# FPGA_PD.net
KiCad netlist of a schematic drawn in Altium Designer
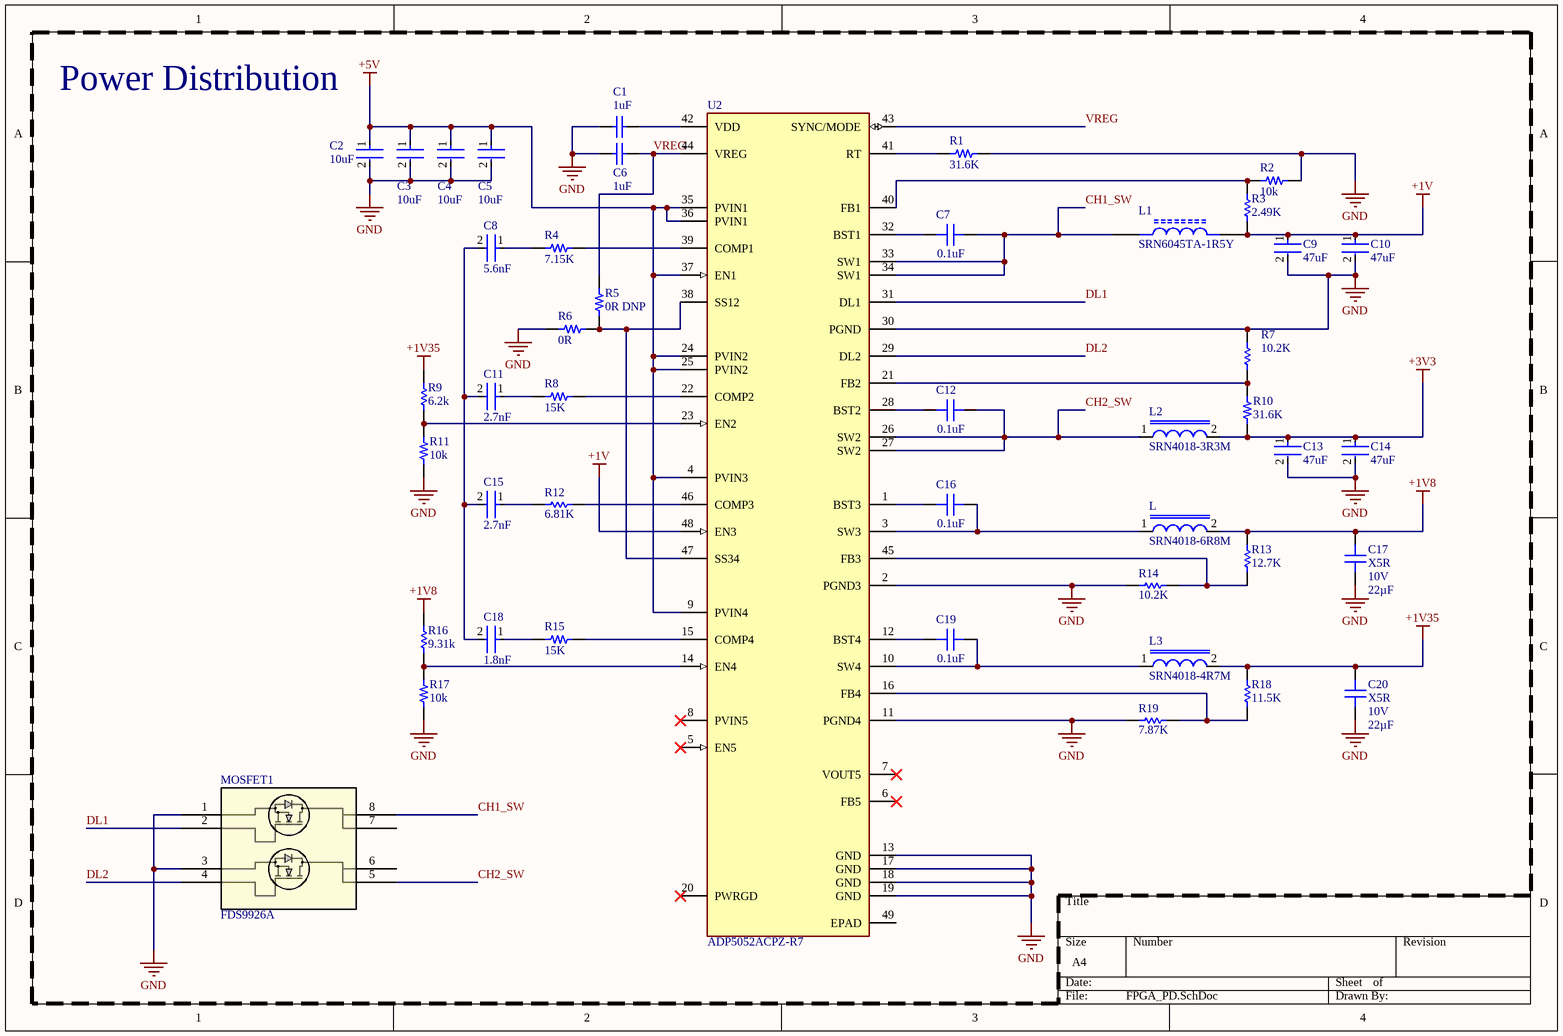
[diagram p0: FPGA_PD.SchDoc]

(export (version "E")
  (design (tool "Eeschema 10.0.6"))
  (components
    (comp (ref "C1")
      (value "1uF")
      (footprint "CAPC1005X55X25LL05T10")
      (fields (field (name "MANUFACTURER") "Murata") (field (name "PART NUMBER") "GRM155R71C104KA88J"))
      (libsource (lib "BIG_FPGA") (part "CMP-2008-03928-1"))
    )
    (comp (ref "C2")
      (value "10uF")
      (footprint "FP-GRM155-0_2-IPC_A")
      (description "Chip Multilayer Ceramic Capacitors for General Purpose, 0402, 10uF, X5R, 15%, 20%, 10V")
      (libsource (lib "BIG_FPGA") (part "CMP-06035-026070-1"))
    )
    (comp (ref "C3")
      (value "10uF")
      (footprint "FP-GRM155-0_2-IPC_A")
      (description "Chip Multilayer Ceramic Capacitors for General Purpose, 0402, 10uF, X5R, 15%, 20%, 10V")
      (libsource (lib "BIG_FPGA") (part "CMP-06035-026070-1"))
    )
    (comp (ref "C4")
      (value "10uF")
      (footprint "FP-GRM155-0_2-IPC_A")
      (description "Chip Multilayer Ceramic Capacitors for General Purpose, 0402, 10uF, X5R, 15%, 20%, 10V")
      (libsource (lib "BIG_FPGA") (part "CMP-06035-026070-1"))
    )
    (comp (ref "C5")
      (value "10uF")
      (footprint "FP-GRM155-0_2-IPC_A")
      (description "Chip Multilayer Ceramic Capacitors for General Purpose, 0402, 10uF, X5R, 15%, 20%, 10V")
      (libsource (lib "BIG_FPGA") (part "CMP-06035-026070-1"))
    )
    (comp (ref "C6")
      (value "1uF")
      (footprint "CAPC1005X55X25LL05T10")
      (fields (field (name "MANUFACTURER") "Murata") (field (name "PART NUMBER") "GRM155R71C104KA88J"))
      (libsource (lib "BIG_FPGA") (part "CMP-2008-03928-1"))
    )
    (comp (ref "C7")
      (value "CAP CER 0.1UF 100V 10% X7R 0603")
      (footprint "CAP 0603_1608")
      (fields (field (name "CAPACITANCE") "0.1uF") (field (name "TOLERANCE") "10%"))
      (libsource (lib "Midnight Sun") (part "Capacitor"))
    )
    (comp (ref "C8")
      (value "5.6nF")
      (footprint "FP-GRM188-0_1-e0_2_0_5-IPC_A")
      (description "Chip Multilayer Ceramic Capacitors for General Purpose, 0603, 5600pF, C0G, 30ppm/°C, 5%, 50V")
      (fields (field (name "TOLERANCE") "5%"))
      (libsource (lib "Altium Content Vault") (part "11868f565c42a9108669ba33697ecf6"))
    )
    (comp (ref "C9")
      (value "47uF")
      (footprint "FP-GRM21B-0_2-MFG")
      (description "CAP CER 47UF 6.3V X5R 0805")
      (fields (field (name "TOLERANCE") "20%") (field (name "VOLTAGE") "6.3V"))
      (libsource (lib "Altium Content Vault") (part "02cd4be3c70576c341d710602a673aa"))
    )
    (comp (ref "C10")
      (value "47uF")
      (footprint "FP-GRM21B-0_2-MFG")
      (description "CAP CER 47UF 6.3V X5R 0805")
      (fields (field (name "TOLERANCE") "20%") (field (name "VOLTAGE") "6.3V"))
      (libsource (lib "Altium Content Vault") (part "02cd4be3c70576c341d710602a673aa"))
    )
    (comp (ref "C11")
      (value "2.7nF")
      (footprint "FP-GRM188-0_1-e0_2_0_5-MFG")
      (description "Chip Multilayer Ceramic Capacitors for General Purpose, 0603, 2700pF, C0G, 30ppm/°C, 5%, 50V")
      (fields (field (name "VOLTAGE") "50V") (field (name "TOLERANCE") "5%"))
      (libsource (lib "Altium Content Vault") (part "11868f565c42a9108669ba33697ecf6"))
    )
    (comp (ref "C12")
      (value "CAP CER 0.1UF 100V 10% X7R 0603")
      (footprint "CAP 0603_1608")
      (fields (field (name "CAPACITANCE") "0.1uF") (field (name "TOLERANCE") "10%"))
      (libsource (lib "Midnight Sun") (part "Capacitor"))
    )
    (comp (ref "C13")
      (value "47uF")
      (footprint "FP-GRM21B-0_2-MFG")
      (description "CAP CER 47UF 6.3V X5R 0805")
      (fields (field (name "TOLERANCE") "20%") (field (name "VOLTAGE") "6.3V"))
      (libsource (lib "Altium Content Vault") (part "02cd4be3c70576c341d710602a673aa"))
    )
    (comp (ref "C14")
      (value "47uF")
      (footprint "FP-GRM21B-0_2-MFG")
      (description "CAP CER 47UF 6.3V X5R 0805")
      (fields (field (name "TOLERANCE") "20%") (field (name "VOLTAGE") "6.3V"))
      (libsource (lib "Altium Content Vault") (part "02cd4be3c70576c341d710602a673aa"))
    )
    (comp (ref "C15")
      (value "2.7nF")
      (footprint "FP-GRM188-0_1-e0_2_0_5-MFG")
      (description "Chip Multilayer Ceramic Capacitors for General Purpose, 0603, 2700pF, C0G, 30ppm/°C, 5%, 50V")
      (fields (field (name "VOLTAGE") "50V") (field (name "TOLERANCE") "5%"))
      (libsource (lib "Altium Content Vault") (part "11868f565c42a9108669ba33697ecf6"))
    )
    (comp (ref "C16")
      (value "CAP CER 0.1UF 100V 10% X7R 0603")
      (footprint "CAP 0603_1608")
      (fields (field (name "CAPACITANCE") "0.1uF") (field (name "TOLERANCE") "10%"))
      (libsource (lib "Midnight Sun") (part "Capacitor"))
    )
    (comp (ref "C17")
      (value "CAP CER 22UF 10V 20% X5R 0603")
      (footprint "CAP 0603_1608")
      (fields
        (field (name "DIELECTRIC CODE") "X5R")
        (field (name "VOLTAGE RATING") "10V")
        (field (name "CAPACITANCE") "22µF")
        (field (name "TOLERANCE") "20%")
      )
      (libsource (lib "Midnight Sun") (part "Capacitor"))
    )
    (comp (ref "C18")
      (value "1.8nF")
      (footprint "FP-GRM188-0_1-e0_2_0_5-IPC_B")
      (description "Chip Multilayer Ceramic Capacitors for General Purpose, 0603, 1800pF, C0G, 30ppm/°C, 5%, 50V")
      (fields (field (name "VOLTAGE") "50V") (field (name "TOLERANCE") "5%"))
      (libsource (lib "Altium Content Vault") (part "11868f565c42a9108669ba33697ecf6"))
    )
    (comp (ref "C19")
      (value "CAP CER 0.1UF 100V 10% X7R 0603")
      (footprint "CAP 0603_1608")
      (fields (field (name "CAPACITANCE") "0.1uF") (field (name "TOLERANCE") "10%"))
      (libsource (lib "Midnight Sun") (part "Capacitor"))
    )
    (comp (ref "C20")
      (value "CAP CER 22UF 10V 20% X5R 0603")
      (footprint "CAP 0603_1608")
      (fields
        (field (name "DIELECTRIC CODE") "X5R")
        (field (name "VOLTAGE RATING") "10V")
        (field (name "CAPACITANCE") "22µF")
        (field (name "TOLERANCE") "20%")
      )
      (libsource (lib "Midnight Sun") (part "Capacitor"))
    )
    (comp (ref "L")
      (value "SRN4018-6R8M")
      (footprint "INDP4040X180N - duplicate")
      (description "6.8ÂµH Semi-Shielded Wirewound Inductor 1.5A 118mOhm Max Nonstandard")
      (fields (field (name "MF") "Bourns"))
      (libsource (lib "BIG_FPGA") (part "SRN4018-6R8M"))
    )
    (comp (ref "L1")
      (value "SRN6045TA-1R5Y")
      (footprint "IND_SRN6045TA-1R5Y")
      (libsource (lib "BIG_FPGA") (part "SRN6045TA-1R5Y"))
    )
    (comp (ref "L2")
      (value "SRN4018-3R3M")
      (footprint "INDP4040X180N - duplicate")
      (description "3.3ÂµH Semi-Shielded Wirewound Inductor 2.2A 66mOhm Max Nonstandard")
      (fields (field (name "MF") "Bourns"))
      (libsource (lib "BIG_FPGA") (part "SRN4018-3R3M"))
    )
    (comp (ref "L3")
      (value "SRN4018-4R7M")
      (footprint "FP-SRN4018-MFG")
      (description "FIXED IND 4.7UH 1.9A 84 MOHM SMD")
      (fields
        (field (name "OCTOPART") "https://octopart.com/srn4018-4r7m-bourns-25452396")
        (field (name "TOLERANCE") "20%")
      )
      (libsource (lib "BIG_FPGA") (part "CMP-07248-000014-1"))
    )
    (comp (ref "MOSFET1")
      (value "FDS9926A")
      (footprint "SOIC8_751EB_ONS-M")
      (description "No Description Available")
      (libsource (lib "BIG_FPGA") (part "FDS9926A"))
    )
    (comp (ref "R1")
      (value "31.6K")
      (footprint "RES 0603_1608")
      (libsource (lib "Midnight Sun") (part "Resistor"))
    )
    (comp (ref "R2")
      (value "10k")
      (footprint "RES 0603_1608")
      (description "10 ±1% 0.1W, 1/10W Chip Resistor 0603 (1608 Metric) Automotive AEC-Q200 Thick Film")
      (libsource (lib "Midnight Sun") (part "Resistor"))
    )
    (comp (ref "R3")
      (value "2.49K")
      (footprint "RESC1608X55X30ML20T20")
      (fields (field (name "PART NUMBER") "ERA3AEB2491V") (field (name "MANUFACTURER") "Panasonic"))
      (libsource (lib "Altium Content Vault") (part "RES"))
    )
    (comp (ref "R4")
      (value "7.15K")
      (footprint "FP-AC0603-IPC_A")
      (description "RES 7.15KΩ 1.00% 0.1W 0603")
      (fields (field (name "TOLERANCE") "1%"))
      (libsource (lib "BIG_FPGA") (part "CMP-03412-024834-2"))
    )
    (comp (ref "R5")
      (value "0R DNP")
      (footprint "RES 0603_1608")
      (description "Fixed Resistor, Metal Glaze/thick Film, 0.1W, 0ohm, Surface Mount, 0603")
      (libsource (lib "Midnight Sun") (part "Resistor"))
    )
    (comp (ref "R6")
      (value "0R")
      (footprint "RES 0603_1608")
      (description "Fixed Resistor, Metal Glaze/thick Film, 0.1W, 0ohm, Surface Mount, 0603")
      (libsource (lib "Midnight Sun") (part "Resistor"))
    )
    (comp (ref "R7")
      (value "10.2K")
      (footprint "RESC1608X55X25LL10T15")
      (description "Chip Resistor, 10.2 KOhm, +/- 1%, 0.1 W, -55 to 155 degC, 0603 (1608 Metric), RoHS, Tape and Reel")
      (fields (field (name "TOLERANCE") "1%") (field (name "MANUFACTURER") "Yageo"))
      (libsource (lib "Altium Content Vault") (part "RES-2"))
    )
    (comp (ref "R8")
      (value "15K")
      (footprint "RES 0603_1608")
      (description "15 kOhms ±1% 0.1W, 1/10W Chip Resistor 0603 (1608 Metric) Moisture Resistant Thick Film")
      (libsource (lib "Midnight Sun") (part "Resistor"))
    )
    (comp (ref "R9")
      (value "6.2k")
      (footprint "RESC1608X55X25ML10T15")
      (fields (field (name "PART NUMBER") "RC0603JR-076K2L") (field (name "MANUFACTURER") "Yageo"))
      (libsource (lib "Altium Content Vault") (part "RES"))
    )
    (comp (ref "R10")
      (value "31.6K")
      (footprint "RES 0603_1608")
      (libsource (lib "Midnight Sun") (part "Resistor"))
    )
    (comp (ref "R11")
      (value "10k")
      (footprint "RES 0603_1608")
      (description "10 ±1% 0.1W, 1/10W Chip Resistor 0603 (1608 Metric) Automotive AEC-Q200 Thick Film")
      (libsource (lib "Midnight Sun") (part "Resistor"))
    )
    (comp (ref "R12")
      (value "6.81K")
      (footprint "RESC1608X55X25ML10T15")
      (fields (field (name "PART NUMBER") "RC0603FR-076K81L") (field (name "MANUFACTURER") "Yageo"))
      (libsource (lib "Altium Content Vault") (part "RES"))
    )
    (comp (ref "R13")
      (value "12.7K")
      (footprint "RESC1608X55X30LL15T15")
      (fields (field (name "MANUFACTURER") "Panasonic") (field (name "PART NUMBER") "ERJ-3EKF1272V"))
      (libsource (lib "Altium Content Vault") (part "RES"))
    )
    (comp (ref "R14")
      (value "10.2K")
      (footprint "RESC1608X55X25LL10T15")
      (description "Chip Resistor, 10.2 KOhm, +/- 1%, 0.1 W, -55 to 155 degC, 0603 (1608 Metric), RoHS, Tape and Reel")
      (fields (field (name "TOLERANCE") "1%") (field (name "MANUFACTURER") "Yageo"))
      (libsource (lib "Altium Content Vault") (part "RES-2"))
    )
    (comp (ref "R15")
      (value "15K")
      (footprint "RES 0603_1608")
      (description "15 kOhms ±1% 0.1W, 1/10W Chip Resistor 0603 (1608 Metric) Moisture Resistant Thick Film")
      (libsource (lib "Midnight Sun") (part "Resistor"))
    )
    (comp (ref "R16")
      (value "9.31k")
      (footprint "RESC1608X55X25LL10T15")
      (fields (field (name "PART NUMBER") "RC0603FR-079K31L") (field (name "MANUFACTURER") "Yageo"))
      (libsource (lib "Altium Content Vault") (part "RES"))
    )
    (comp (ref "R17")
      (value "10k")
      (footprint "RES 0603_1608")
      (description "10 ±1% 0.1W, 1/10W Chip Resistor 0603 (1608 Metric) Automotive AEC-Q200 Thick Film")
      (libsource (lib "Midnight Sun") (part "Resistor"))
    )
    (comp (ref "R18")
      (value "11.5K")
      (footprint "RESC1608X55X25LL10T15")
      (fields (field (name "MANUFACTURER") "Yageo") (field (name "PART NUMBER") "RC0603FR-0711K5L"))
      (libsource (lib "Altium Content Vault") (part "RES"))
    )
    (comp (ref "R19")
      (value "7.87K")
      (footprint "RESC1608X55X25NL10T15")
      (fields (field (name "PART NUMBER") "RC0603FR-07787KL") (field (name "MANUFACTURER") "Yageo"))
      (libsource (lib "Altium Content Vault") (part "RES"))
    )
    (comp (ref "U2")
      (value "ADP5052ACPZ-R7")
      (footprint "FP-CP-48-13-IPC_A")
      (libsource (lib "Altium Content Vault") (part "c99ea894cd2d839e347de8f837bd5fd"))
    )
  )
  (nets
    (net (code "1") (name "+1V") (class "Default")
      (node (ref "C10") (pin "1") (pinfunction "1_1") (pintype "passive"))
      (node (ref "C9") (pin "1") (pinfunction "1_1") (pintype "passive"))
      (node (ref "L1") (pin "2") (pinfunction "2_2") (pintype "passive"))
      (node (ref "R3") (pin "1") (pinfunction "1_1") (pintype "passive"))
      (node (ref "U2") (pin "48") (pinfunction "EN3_48") (pintype "input"))
    )
    (net (code "2") (name "+1V8") (class "Default")
      (node (ref "C17") (pin "1") (pinfunction "1_1") (pintype "passive"))
      (node (ref "L") (pin "2") (pinfunction "2_2") (pintype "passive"))
      (node (ref "R13") (pin "2") (pinfunction "2_2") (pintype "passive"))
      (node (ref "R16") (pin "1") (pinfunction "1_1") (pintype "passive"))
    )
    (net (code "3") (name "+1V35") (class "Default")
      (node (ref "C20") (pin "1") (pinfunction "1_1") (pintype "passive"))
      (node (ref "L3") (pin "2") (pinfunction "2_2") (pintype "passive"))
      (node (ref "R18") (pin "1") (pinfunction "1_1") (pintype "passive"))
      (node (ref "R9") (pin "1") (pinfunction "1_1") (pintype "passive"))
    )
    (net (code "4") (name "+3V3") (class "Default")
      (node (ref "C13") (pin "1") (pinfunction "1_1") (pintype "passive"))
      (node (ref "C14") (pin "1") (pinfunction "1_1") (pintype "passive"))
      (node (ref "L2") (pin "2") (pinfunction "2_2") (pintype "passive"))
      (node (ref "R10") (pin "2") (pinfunction "2_2") (pintype "passive"))
    )
    (net (code "5") (name "+5V") (class "Default")
      (node (ref "C2") (pin "1") (pinfunction "1_1") (pintype "passive"))
      (node (ref "C3") (pin "1") (pinfunction "1_1") (pintype "passive"))
      (node (ref "C4") (pin "1") (pinfunction "1_1") (pintype "passive"))
      (node (ref "C5") (pin "1") (pinfunction "1_1") (pintype "passive"))
      (node (ref "U2") (pin "24") (pinfunction "PVIN2_24") (pintype "power_in"))
      (node (ref "U2") (pin "25") (pinfunction "PVIN2_25") (pintype "power_in"))
      (node (ref "U2") (pin "35") (pinfunction "PVIN1_35") (pintype "power_in"))
      (node (ref "U2") (pin "36") (pinfunction "PVIN1_36") (pintype "power_in"))
      (node (ref "U2") (pin "37") (pinfunction "EN1_37") (pintype "input"))
      (node (ref "U2") (pin "4") (pinfunction "PVIN3_4") (pintype "power_in"))
      (node (ref "U2") (pin "9") (pinfunction "PVIN4_9") (pintype "power_in"))
    )
    (net (code "6") (name "/CH1_SW") (class "Default")
      (node (ref "C7") (pin "1") (pinfunction "1_1") (pintype "passive"))
      (node (ref "L1") (pin "1") (pinfunction "1_1") (pintype "passive"))
      (node (ref "MOSFET1") (pin "8") (pinfunction "8_8") (pintype "passive"))
      (node (ref "U2") (pin "33") (pinfunction "SW1_33") (pintype "power_in"))
      (node (ref "U2") (pin "34") (pinfunction "SW1_34") (pintype "power_in"))
    )
    (net (code "7") (name "/CH2_SW") (class "Default")
      (node (ref "C12") (pin "1") (pinfunction "1_1") (pintype "passive"))
      (node (ref "L2") (pin "1") (pinfunction "1_1") (pintype "passive"))
      (node (ref "MOSFET1") (pin "5") (pinfunction "5_5") (pintype "passive"))
      (node (ref "U2") (pin "26") (pinfunction "SW2_26") (pintype "power_in"))
      (node (ref "U2") (pin "27") (pinfunction "SW2_27") (pintype "power_in"))
    )
    (net (code "8") (name "/DL1") (class "Default")
      (node (ref "MOSFET1") (pin "2") (pinfunction "2_2") (pintype "passive"))
      (node (ref "U2") (pin "31") (pinfunction "DL1_31") (pintype "passive"))
    )
    (net (code "9") (name "/DL2") (class "Default")
      (node (ref "MOSFET1") (pin "4") (pinfunction "4_4") (pintype "passive"))
      (node (ref "U2") (pin "29") (pinfunction "DL2_29") (pintype "passive"))
    )
    (net (code "10") (name "/VREG") (class "Default")
      (node (ref "C6") (pin "2") (pinfunction "2_2") (pintype "passive"))
      (node (ref "R5") (pin "2") (pinfunction "2_2") (pintype "passive"))
      (node (ref "U2") (pin "43") (pinfunction "SYNC/MODE_43") (pintype "bidirectional"))
      (node (ref "U2") (pin "44") (pinfunction "VREG_44") (pintype "power_in"))
    )
    (net (code "11") (name "GND") (class "Default")
      (node (ref "C1") (pin "1") (pinfunction "1_1") (pintype "passive"))
      (node (ref "C10") (pin "2") (pinfunction "2_2") (pintype "passive"))
      (node (ref "C13") (pin "2") (pinfunction "2_2") (pintype "passive"))
      (node (ref "C14") (pin "2") (pinfunction "2_2") (pintype "passive"))
      (node (ref "C17") (pin "2") (pinfunction "2_2") (pintype "passive"))
      (node (ref "C2") (pin "2") (pinfunction "2_2") (pintype "passive"))
      (node (ref "C20") (pin "2") (pinfunction "2_2") (pintype "passive"))
      (node (ref "C3") (pin "2") (pinfunction "2_2") (pintype "passive"))
      (node (ref "C4") (pin "2") (pinfunction "2_2") (pintype "passive"))
      (node (ref "C5") (pin "2") (pinfunction "2_2") (pintype "passive"))
      (node (ref "C6") (pin "1") (pinfunction "1_1") (pintype "passive"))
      (node (ref "C9") (pin "2") (pinfunction "2_2") (pintype "passive"))
      (node (ref "MOSFET1") (pin "1") (pinfunction "1_1") (pintype "passive"))
      (node (ref "MOSFET1") (pin "3") (pinfunction "3_3") (pintype "passive"))
      (node (ref "R1") (pin "2") (pinfunction "2_2") (pintype "passive"))
      (node (ref "R11") (pin "2") (pinfunction "2_2") (pintype "passive"))
      (node (ref "R14") (pin "2") (pinfunction "2_2") (pintype "passive"))
      (node (ref "R17") (pin "2") (pinfunction "2_2") (pintype "passive"))
      (node (ref "R19") (pin "1") (pinfunction "1_1") (pintype "passive"))
      (node (ref "R2") (pin "1") (pinfunction "1_1") (pintype "passive"))
      (node (ref "R6") (pin "1") (pinfunction "1_1") (pintype "passive"))
      (node (ref "R7") (pin "1") (pinfunction "1_1") (pintype "passive"))
      (node (ref "U2") (pin "11") (pinfunction "PGND4_11") (pintype "power_in"))
      (node (ref "U2") (pin "13") (pinfunction "GND_13") (pintype "power_in"))
      (node (ref "U2") (pin "17") (pinfunction "GND_17") (pintype "power_in"))
      (node (ref "U2") (pin "18") (pinfunction "GND_18") (pintype "power_in"))
      (node (ref "U2") (pin "19") (pinfunction "GND_19") (pintype "power_in"))
      (node (ref "U2") (pin "2") (pinfunction "PGND3_2") (pintype "power_in"))
      (node (ref "U2") (pin "30") (pinfunction "PGND_30") (pintype "power_in"))
    )
    (net (code "12") (name "Net-(C8-Pad1)") (class "Default")
      (node (ref "C8") (pin "1") (pinfunction "1_1") (pintype "passive"))
      (node (ref "R4") (pin "1") (pinfunction "1_1") (pintype "passive"))
    )
    (net (code "13") (name "Net-(C11-Pad1)") (class "Default")
      (node (ref "C11") (pin "1") (pinfunction "1_1") (pintype "passive"))
      (node (ref "R8") (pin "1") (pinfunction "1_1") (pintype "passive"))
    )
    (net (code "14") (name "Net-(C11-Pad2)") (class "Default")
      (node (ref "C11") (pin "2") (pinfunction "2_2") (pintype "passive"))
      (node (ref "C15") (pin "2") (pinfunction "2_2") (pintype "passive"))
      (node (ref "C18") (pin "2") (pinfunction "2_2") (pintype "passive"))
      (node (ref "C8") (pin "2") (pinfunction "2_2") (pintype "passive"))
    )
    (net (code "15") (name "Net-(C15-Pad1)") (class "Default")
      (node (ref "C15") (pin "1") (pinfunction "1_1") (pintype "passive"))
      (node (ref "R12") (pin "1") (pinfunction "1_1") (pintype "passive"))
    )
    (net (code "16") (name "Net-(C18-Pad1)") (class "Default")
      (node (ref "C18") (pin "1") (pinfunction "1_1") (pintype "passive"))
      (node (ref "R15") (pin "1") (pinfunction "1_1") (pintype "passive"))
    )
    (net (code "17") (name "Net-(U2-BST1)") (class "Default")
      (node (ref "C7") (pin "2") (pinfunction "2_2") (pintype "passive"))
      (node (ref "U2") (pin "32") (pinfunction "BST1_32") (pintype "power_in"))
    )
    (net (code "18") (name "Net-(U2-BST2)") (class "Default")
      (node (ref "C12") (pin "2") (pinfunction "2_2") (pintype "passive"))
      (node (ref "U2") (pin "28") (pinfunction "BST2_28") (pintype "power_in"))
    )
    (net (code "19") (name "Net-(U2-BST3)") (class "Default")
      (node (ref "C16") (pin "2") (pinfunction "2_2") (pintype "passive"))
      (node (ref "U2") (pin "1") (pinfunction "BST3_1") (pintype "power_in"))
    )
    (net (code "20") (name "Net-(U2-BST4)") (class "Default")
      (node (ref "C19") (pin "2") (pinfunction "2_2") (pintype "passive"))
      (node (ref "U2") (pin "12") (pinfunction "BST4_12") (pintype "power_in"))
    )
    (net (code "21") (name "Net-(U2-COMP1)") (class "Default")
      (node (ref "R4") (pin "2") (pinfunction "2_2") (pintype "passive"))
      (node (ref "U2") (pin "39") (pinfunction "COMP1_39") (pintype "passive"))
    )
    (net (code "22") (name "Net-(U2-COMP2)") (class "Default")
      (node (ref "R8") (pin "2") (pinfunction "2_2") (pintype "passive"))
      (node (ref "U2") (pin "22") (pinfunction "COMP2_22") (pintype "passive"))
    )
    (net (code "23") (name "Net-(U2-COMP3)") (class "Default")
      (node (ref "R12") (pin "2") (pinfunction "2_2") (pintype "passive"))
      (node (ref "U2") (pin "46") (pinfunction "COMP3_46") (pintype "passive"))
    )
    (net (code "24") (name "Net-(U2-COMP4)") (class "Default")
      (node (ref "R15") (pin "2") (pinfunction "2_2") (pintype "passive"))
      (node (ref "U2") (pin "15") (pinfunction "COMP4_15") (pintype "passive"))
    )
    (net (code "25") (name "Net-(U2-EN2)") (class "Default")
      (node (ref "R11") (pin "1") (pinfunction "1_1") (pintype "passive"))
      (node (ref "R9") (pin "2") (pinfunction "2_2") (pintype "passive"))
      (node (ref "U2") (pin "23") (pinfunction "EN2_23") (pintype "input"))
    )
    (net (code "26") (name "Net-(U2-EN4)") (class "Default")
      (node (ref "R16") (pin "2") (pinfunction "2_2") (pintype "passive"))
      (node (ref "R17") (pin "1") (pinfunction "1_1") (pintype "passive"))
      (node (ref "U2") (pin "14") (pinfunction "EN4_14") (pintype "input"))
    )
    (net (code "27") (name "Net-(U2-FB1)") (class "Default")
      (node (ref "R2") (pin "2") (pinfunction "2_2") (pintype "passive"))
      (node (ref "R3") (pin "2") (pinfunction "2_2") (pintype "passive"))
      (node (ref "U2") (pin "40") (pinfunction "FB1_40") (pintype "passive"))
    )
    (net (code "28") (name "Net-(U2-FB2)") (class "Default")
      (node (ref "R10") (pin "1") (pinfunction "1_1") (pintype "passive"))
      (node (ref "R7") (pin "2") (pinfunction "2_2") (pintype "passive"))
      (node (ref "U2") (pin "21") (pinfunction "FB2_21") (pintype "passive"))
    )
    (net (code "29") (name "Net-(U2-FB3)") (class "Default")
      (node (ref "R13") (pin "1") (pinfunction "1_1") (pintype "passive"))
      (node (ref "R14") (pin "1") (pinfunction "1_1") (pintype "passive"))
      (node (ref "U2") (pin "45") (pinfunction "FB3_45") (pintype "passive"))
    )
    (net (code "30") (name "Net-(U2-FB4)") (class "Default")
      (node (ref "R18") (pin "2") (pinfunction "2_2") (pintype "passive"))
      (node (ref "R19") (pin "2") (pinfunction "2_2") (pintype "passive"))
      (node (ref "U2") (pin "16") (pinfunction "FB4_16") (pintype "passive"))
    )
    (net (code "31") (name "Net-(U2-RT)") (class "Default")
      (node (ref "R1") (pin "1") (pinfunction "1_1") (pintype "passive"))
      (node (ref "U2") (pin "41") (pinfunction "RT_41") (pintype "passive"))
    )
    (net (code "32") (name "Net-(U2-SS12)") (class "Default")
      (node (ref "R5") (pin "1") (pinfunction "1_1") (pintype "passive"))
      (node (ref "R6") (pin "2") (pinfunction "2_2") (pintype "passive"))
      (node (ref "U2") (pin "38") (pinfunction "SS12_38") (pintype "passive"))
      (node (ref "U2") (pin "47") (pinfunction "SS34_47") (pintype "passive"))
    )
    (net (code "33") (name "Net-(U2-SW3)") (class "Default")
      (node (ref "C16") (pin "1") (pinfunction "1_1") (pintype "passive"))
      (node (ref "L") (pin "1") (pinfunction "1_1") (pintype "passive"))
      (node (ref "U2") (pin "3") (pinfunction "SW3_3") (pintype "power_in"))
    )
    (net (code "34") (name "Net-(U2-SW4)") (class "Default")
      (node (ref "C19") (pin "1") (pinfunction "1_1") (pintype "passive"))
      (node (ref "L3") (pin "1") (pinfunction "1_1") (pintype "passive"))
      (node (ref "U2") (pin "10") (pinfunction "SW4_10") (pintype "power_in"))
    )
    (net (code "35") (name "Net-(U2-VDD)") (class "Default")
      (node (ref "C1") (pin "2") (pinfunction "2_2") (pintype "passive"))
      (node (ref "U2") (pin "42") (pinfunction "VDD_42") (pintype "power_in"))
    )
    (net (code "36") (name "unconnected-(MOSFET1-Pad6)") (class "Default")
      (node (ref "MOSFET1") (pin "6") (pinfunction "6_6") (pintype "passive"))
    )
    (net (code "37") (name "unconnected-(MOSFET1-Pad7)") (class "Default")
      (node (ref "MOSFET1") (pin "7") (pinfunction "7_7") (pintype "passive"))
    )
    (net (code "38") (name "unconnected-(U2-EN5-Pad5)") (class "Default")
      (node (ref "U2") (pin "5") (pinfunction "EN5_5") (pintype "input+no_connect"))
    )
    (net (code "39") (name "unconnected-(U2-EPAD-Pad49)") (class "Default")
      (node (ref "U2") (pin "49") (pinfunction "EPAD_49") (pintype "power_in"))
    )
    (net (code "40") (name "unconnected-(U2-FB5-Pad6)") (class "Default")
      (node (ref "U2") (pin "6") (pinfunction "FB5_6") (pintype "passive+no_connect"))
    )
    (net (code "41") (name "unconnected-(U2-PVIN5-Pad8)") (class "Default")
      (node (ref "U2") (pin "8") (pinfunction "PVIN5_8") (pintype "power_in+no_connect"))
    )
    (net (code "42") (name "unconnected-(U2-PWRGD-Pad20)") (class "Default")
      (node (ref "U2") (pin "20") (pinfunction "PWRGD_20") (pintype "open_collector+no_connect"))
    )
    (net (code "43") (name "unconnected-(U2-VOUT5-Pad7)") (class "Default")
      (node (ref "U2") (pin "7") (pinfunction "VOUT5_7") (pintype "power_in+no_connect"))
    )
  )
)
